# accra_conditioner.net
KiCad netlist of a schematic drawn in EAGLE
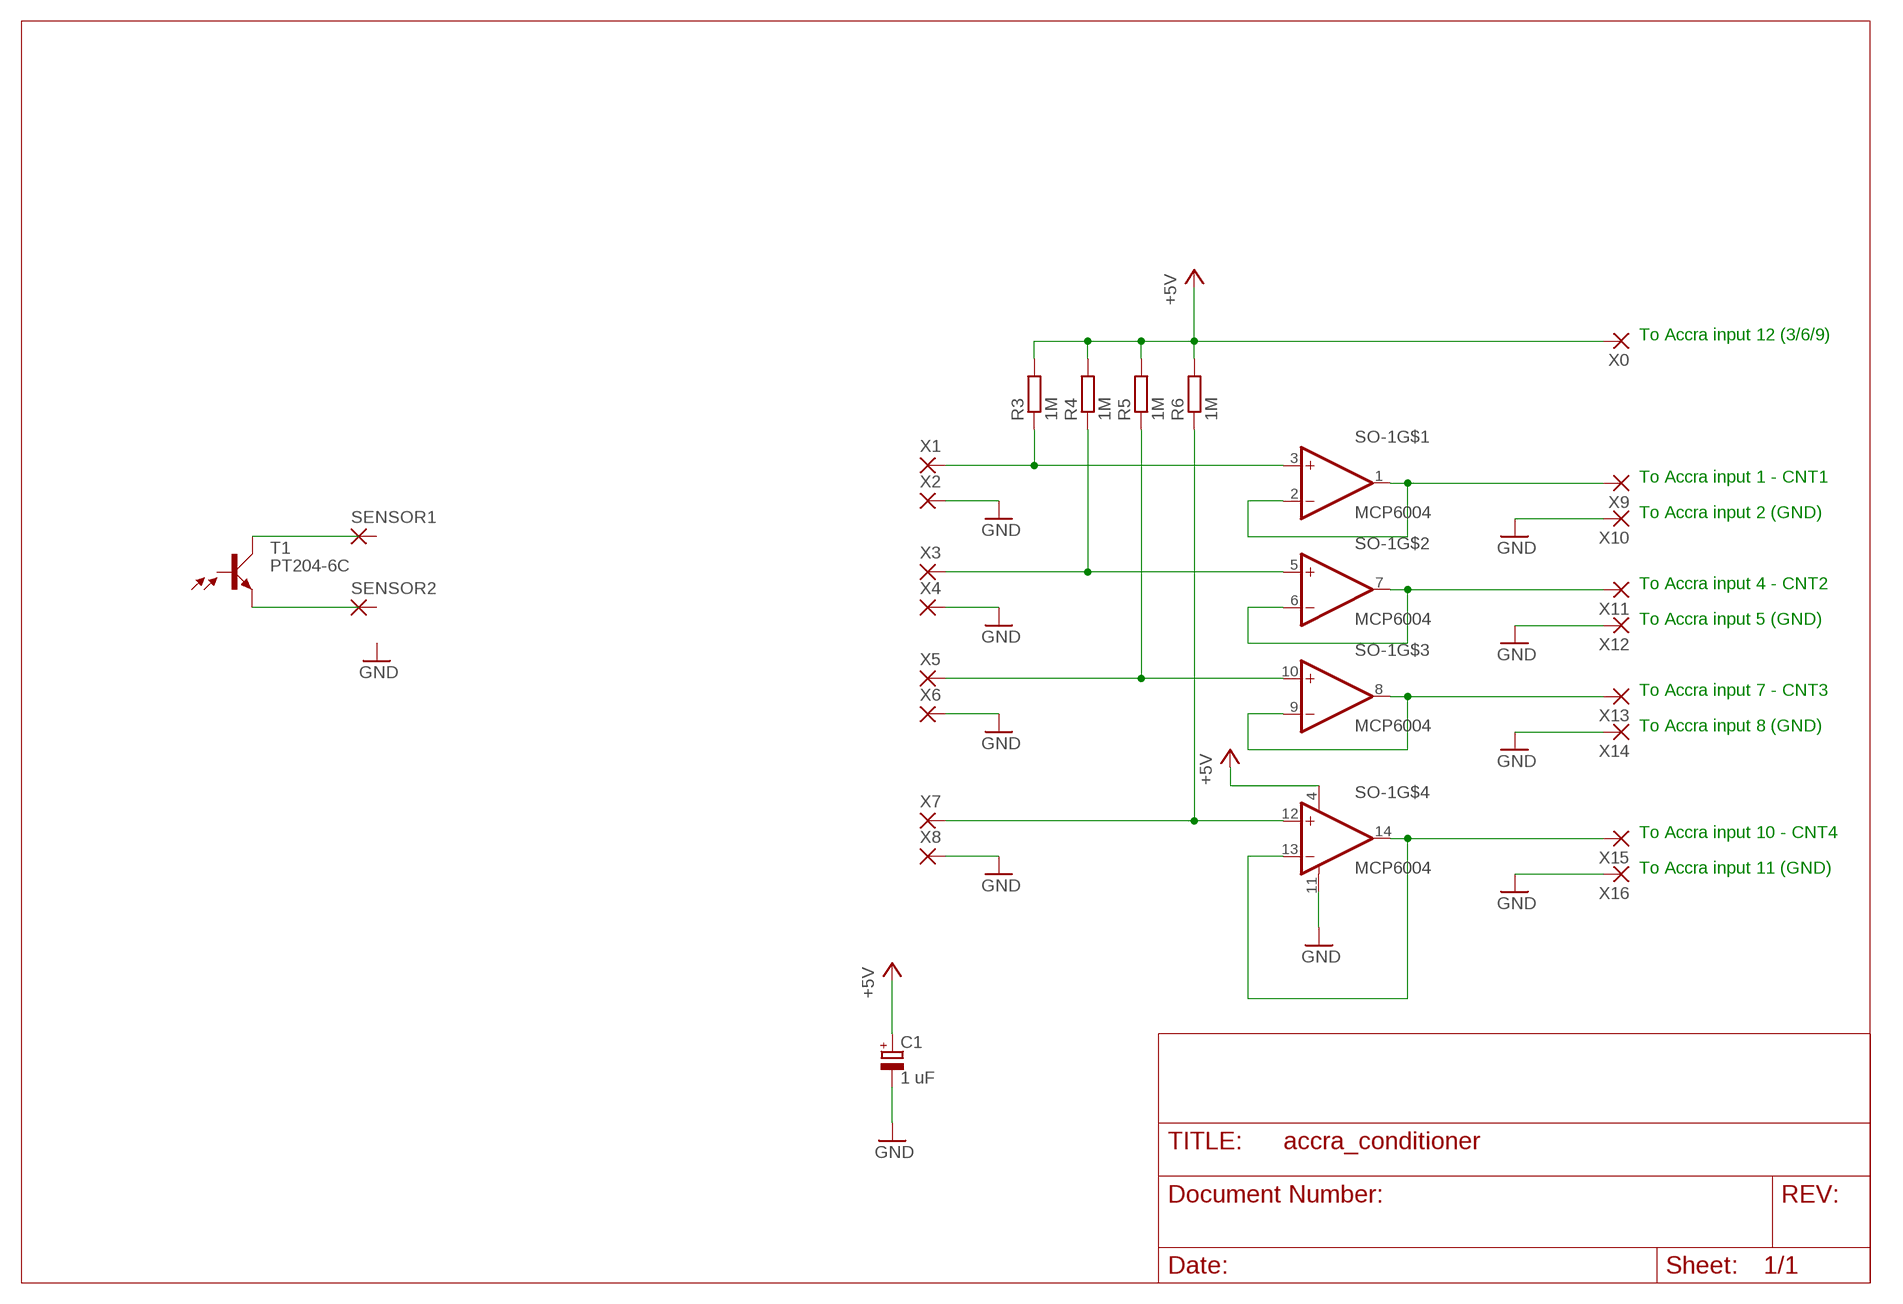
[diagram p0: schematic, sheet 1]

(export (version "E")
  (design (tool "Eeschema 10.0.6"))
  (components
    (comp (ref "C1")
      (value "1 uF")
      (footprint "eagle-import:E2,5-5")
      (libsource (lib "eagle-import") (part "CPOL-EUE2.5-5"))
    )
    (comp (ref "R3")
      (value "1M")
      (footprint "eagle-import:0207_10")
      (libsource (lib "eagle-import") (part "R-EU_0207/10"))
    )
    (comp (ref "R4")
      (value "1M")
      (footprint "eagle-import:0207_10")
      (libsource (lib "eagle-import") (part "R-EU_0207/10"))
    )
    (comp (ref "R5")
      (value "1M")
      (footprint "eagle-import:0207_10")
      (libsource (lib "eagle-import") (part "R-EU_0207/10"))
    )
    (comp (ref "R6")
      (value "1M")
      (footprint "eagle-import:0207_10")
      (libsource (lib "eagle-import") (part "R-EU_0207/10"))
    )
    (comp (ref "SENSOR1")
      (value "WIREPAD1,6/0,8")
      (footprint "eagle-import:1,6_0,8")
      (libsource (lib "eagle-import") (part "WIREPAD1,6/0,8"))
    )
    (comp (ref "SENSOR2")
      (value "WIREPAD1,6/0,8")
      (footprint "eagle-import:1,6_0,8")
      (libsource (lib "eagle-import") (part "WIREPAD1,6/0,8"))
    )
    (comp (ref "SO-1")
      (value "MCP6004")
      (footprint "eagle-import:SO-14")
      (libsource (lib "eagle-import") (part "MCP6004"))
    )
    (comp (ref "T1")
      (value "PT204-6C")
      (footprint "eagle-import:BP103")
      (libsource (lib "eagle-import") (part "BP103"))
    )
    (comp (ref "X0")
      (value "WIREPAD1,6/0,8")
      (footprint "eagle-import:1,6_0,8")
      (libsource (lib "eagle-import") (part "WIREPAD1,6/0,8"))
    )
    (comp (ref "X1")
      (value "WIREPAD1,6/0,8")
      (footprint "eagle-import:1,6_0,8")
      (libsource (lib "eagle-import") (part "WIREPAD1,6/0,8"))
    )
    (comp (ref "X2")
      (value "WIREPAD1,6/0,8")
      (footprint "eagle-import:1,6_0,8")
      (libsource (lib "eagle-import") (part "WIREPAD1,6/0,8"))
    )
    (comp (ref "X3")
      (value "WIREPAD1,6/0,8")
      (footprint "eagle-import:1,6_0,8")
      (libsource (lib "eagle-import") (part "WIREPAD1,6/0,8"))
    )
    (comp (ref "X4")
      (value "WIREPAD1,6/0,8")
      (footprint "eagle-import:1,6_0,8")
      (libsource (lib "eagle-import") (part "WIREPAD1,6/0,8"))
    )
    (comp (ref "X5")
      (value "WIREPAD1,6/0,8")
      (footprint "eagle-import:1,6_0,8")
      (libsource (lib "eagle-import") (part "WIREPAD1,6/0,8"))
    )
    (comp (ref "X6")
      (value "WIREPAD1,6/0,8")
      (footprint "eagle-import:1,6_0,8")
      (libsource (lib "eagle-import") (part "WIREPAD1,6/0,8"))
    )
    (comp (ref "X7")
      (value "WIREPAD1,6/0,8")
      (footprint "eagle-import:1,6_0,8")
      (libsource (lib "eagle-import") (part "WIREPAD1,6/0,8"))
    )
    (comp (ref "X8")
      (value "WIREPAD1,6/0,8")
      (footprint "eagle-import:1,6_0,8")
      (libsource (lib "eagle-import") (part "WIREPAD1,6/0,8"))
    )
    (comp (ref "X9")
      (value "WIREPAD1,6/0,8")
      (footprint "eagle-import:1,6_0,8")
      (libsource (lib "eagle-import") (part "WIREPAD1,6/0,8"))
    )
    (comp (ref "X10")
      (value "WIREPAD1,6/0,8")
      (footprint "eagle-import:1,6_0,8")
      (libsource (lib "eagle-import") (part "WIREPAD1,6/0,8"))
    )
    (comp (ref "X11")
      (value "WIREPAD1,6/0,8")
      (footprint "eagle-import:1,6_0,8")
      (libsource (lib "eagle-import") (part "WIREPAD1,6/0,8"))
    )
    (comp (ref "X12")
      (value "WIREPAD1,6/0,8")
      (footprint "eagle-import:1,6_0,8")
      (libsource (lib "eagle-import") (part "WIREPAD1,6/0,8"))
    )
    (comp (ref "X13")
      (value "WIREPAD1,6/0,8")
      (footprint "eagle-import:1,6_0,8")
      (libsource (lib "eagle-import") (part "WIREPAD1,6/0,8"))
    )
    (comp (ref "X14")
      (value "WIREPAD1,6/0,8")
      (footprint "eagle-import:1,6_0,8")
      (libsource (lib "eagle-import") (part "WIREPAD1,6/0,8"))
    )
    (comp (ref "X15")
      (value "WIREPAD1,6/0,8")
      (footprint "eagle-import:1,6_0,8")
      (libsource (lib "eagle-import") (part "WIREPAD1,6/0,8"))
    )
    (comp (ref "X16")
      (value "WIREPAD1,6/0,8")
      (footprint "eagle-import:1,6_0,8")
      (libsource (lib "eagle-import") (part "WIREPAD1,6/0,8"))
    )
  )
  (nets
    (net (code "1") (name "+5V") (class "Default")
      (node (ref "C1") (pin "+") (pinfunction "+_+") (pintype "passive"))
      (node (ref "R3") (pin "2") (pinfunction "2_2") (pintype "passive"))
      (node (ref "R4") (pin "2") (pinfunction "2_2") (pintype "passive"))
      (node (ref "R5") (pin "2") (pinfunction "2_2") (pintype "passive"))
      (node (ref "R6") (pin "2") (pinfunction "2_2") (pintype "passive"))
      (node (ref "SO-1") (pin "4") (pinfunction "V+_4") (pintype "power_in"))
      (node (ref "X0") (pin "1") (pinfunction "P_1") (pintype "passive"))
    )
    (net (code "2") (name "GND") (class "Default")
      (node (ref "C1") (pin "-") (pinfunction "-_-") (pintype "passive"))
      (node (ref "SO-1") (pin "11") (pinfunction "V-_11") (pintype "power_in"))
      (node (ref "X10") (pin "1") (pinfunction "P_1") (pintype "passive"))
      (node (ref "X12") (pin "1") (pinfunction "P_1") (pintype "passive"))
      (node (ref "X14") (pin "1") (pinfunction "P_1") (pintype "passive"))
      (node (ref "X16") (pin "1") (pinfunction "P_1") (pintype "passive"))
      (node (ref "X2") (pin "1") (pinfunction "P_1") (pintype "passive"))
      (node (ref "X4") (pin "1") (pinfunction "P_1") (pintype "passive"))
      (node (ref "X6") (pin "1") (pinfunction "P_1") (pintype "passive"))
      (node (ref "X8") (pin "1") (pinfunction "P_1") (pintype "passive"))
    )
    (net (code "3") (name "Net-(SO-1A-+IN)") (class "Default")
      (node (ref "R3") (pin "1") (pinfunction "1_1") (pintype "passive"))
      (node (ref "SO-1") (pin "3") (pinfunction "+IN_3") (pintype "input"))
      (node (ref "X1") (pin "1") (pinfunction "P_1") (pintype "passive"))
    )
    (net (code "4") (name "Net-(SO-1A--IN)") (class "Default")
      (node (ref "SO-1") (pin "1") (pinfunction "OUT_1") (pintype "output"))
      (node (ref "SO-1") (pin "2") (pinfunction "-IN_2") (pintype "input"))
      (node (ref "X9") (pin "1") (pinfunction "P_1") (pintype "passive"))
    )
    (net (code "5") (name "Net-(SO-1B-+IN)") (class "Default")
      (node (ref "R4") (pin "1") (pinfunction "1_1") (pintype "passive"))
      (node (ref "SO-1") (pin "5") (pinfunction "+IN_5") (pintype "input"))
      (node (ref "X3") (pin "1") (pinfunction "P_1") (pintype "passive"))
    )
    (net (code "6") (name "Net-(SO-1B--IN)") (class "Default")
      (node (ref "SO-1") (pin "6") (pinfunction "-IN_6") (pintype "input"))
      (node (ref "SO-1") (pin "7") (pinfunction "OUT_7") (pintype "output"))
      (node (ref "X11") (pin "1") (pinfunction "P_1") (pintype "passive"))
    )
    (net (code "7") (name "Net-(SO-1C-+IN)") (class "Default")
      (node (ref "R5") (pin "1") (pinfunction "1_1") (pintype "passive"))
      (node (ref "SO-1") (pin "10") (pinfunction "+IN_10") (pintype "input"))
      (node (ref "X5") (pin "1") (pinfunction "P_1") (pintype "passive"))
    )
    (net (code "8") (name "Net-(SO-1C--IN)") (class "Default")
      (node (ref "SO-1") (pin "8") (pinfunction "OUT_8") (pintype "output"))
      (node (ref "SO-1") (pin "9") (pinfunction "-IN_9") (pintype "input"))
      (node (ref "X13") (pin "1") (pinfunction "P_1") (pintype "passive"))
    )
    (net (code "9") (name "Net-(SO-1D-+IN)") (class "Default")
      (node (ref "R6") (pin "1") (pinfunction "1_1") (pintype "passive"))
      (node (ref "SO-1") (pin "12") (pinfunction "+IN_12") (pintype "input"))
      (node (ref "X7") (pin "1") (pinfunction "P_1") (pintype "passive"))
    )
    (net (code "10") (name "Net-(SO-1D--IN)") (class "Default")
      (node (ref "SO-1") (pin "13") (pinfunction "-IN_13") (pintype "input"))
      (node (ref "SO-1") (pin "14") (pinfunction "OUT_14") (pintype "output"))
      (node (ref "X15") (pin "1") (pinfunction "P_1") (pintype "passive"))
    )
    (net (code "11") (name "unconnected-(SENSOR1-P-Pad1)") (class "Default")
      (node (ref "SENSOR1") (pin "1") (pinfunction "P_1") (pintype "passive"))
    )
    (net (code "12") (name "unconnected-(SENSOR2-P-Pad1)") (class "Default")
      (node (ref "SENSOR2") (pin "1") (pinfunction "P_1") (pintype "passive"))
    )
    (net (code "13") (name "unconnected-(T1-PadB)") (class "Default")
      (node (ref "T1") (pin "B") (pinfunction "B_B") (pintype "passive"))
    )
    (net (code "14") (name "unconnected-(T1-PadC)") (class "Default")
      (node (ref "T1") (pin "C") (pinfunction "C_C") (pintype "passive"))
    )
    (net (code "15") (name "unconnected-(T1-PadE)") (class "Default")
      (node (ref "T1") (pin "E") (pinfunction "E_E") (pintype "passive"))
    )
  )
)
